# Current_Sense_Schematic.net
KiCad netlist of a schematic drawn in Altium Designer
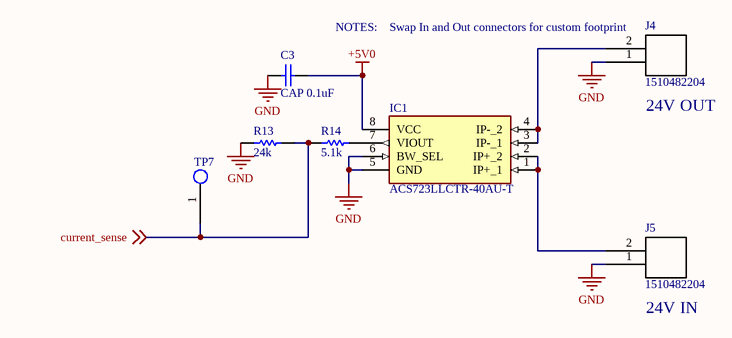
[diagram p0: Current Sense Schematic.SchDoc]

(export (version "E")
  (design (tool "Eeschema 10.0.6"))
  (components
    (comp (ref "C3")
      (value "CAP 0.1uF")
      (footprint "CAPC0805(2012)75_L")
      (description "CAP 2.7pF 50V ±0.1pF 0805 (2012 Metric) Thickness 0.75mm SMD")
      (fields (field (name "TOLERANCE") "Â±0.1pF"))
      (libsource (lib "Integrated_Library - 12.01.19 - 13.05") (part "CMP-1036-00339-1"))
    )
    (comp (ref "IC1")
      (value "ACS723LLCTR-40AU-T")
      (footprint "SOT127P600X175-8N")
      (description "Integrated Circuit")
      (libsource (lib "SamacSys") (part "ACS723LLCTR-40AU-T"))
    )
    (comp (ref "J4")
      (value "1510482204")
      (footprint "1510482204")
      (description "Molex 6.5MM 2 pin connector, used for power connections. P/N 1510482204 and similar models.")
      (libsource (lib "Molex 6.5MM  power connectors, 1510482204 etc.") (part "1510482204"))
    )
    (comp (ref "J5")
      (value "1510482204")
      (footprint "1510482204")
      (description "Molex 6.5MM 2 pin connector, used for power connections. P/N 1510482204 and similar models.")
      (libsource (lib "Molex 6.5MM  power connectors, 1510482204 etc.") (part "1510482204"))
    )
    (comp (ref "R13")
      (value "24k")
      (footprint "RESC2013X70X40LL20T20")
      (description "RES SMD 150K OHM 1% 1/8W 0805")
      (fields (field (name "MANUFACTURER") "Panasonic") (field (name "PART NUMBER") "ERJ-6ENF1503V"))
      (libsource (lib "Altium Content Vault") (part "RES"))
    )
    (comp (ref "R14")
      (value "5.1k")
      (footprint "RESC2013X70X40LL20T20")
      (description "RES SMD 150K OHM 1% 1/8W 0805")
      (fields (field (name "MANUFACTURER") "Panasonic") (field (name "PART NUMBER") "ERJ-6ENF1503V"))
      (libsource (lib "Altium Content Vault") (part "RES"))
    )
    (comp (ref "TP7")
      (value "Test Point")
      (footprint "Test Point Through-hole")
      (libsource (lib "Husky Robotics Standard Library 2019-2020") (part "Test Point"))
    )
  )
  (nets
    (net (code "1") (name "+5V0") (class "Default")
      (node (ref "C3") (pin "2") (pinfunction "2_2") (pintype "passive"))
      (node (ref "IC1") (pin "8") (pinfunction "VCC_8") (pintype "power_in"))
    )
    (net (code "2") (name "GND") (class "Default")
      (node (ref "C3") (pin "1") (pinfunction "1_1") (pintype "passive"))
      (node (ref "IC1") (pin "5") (pinfunction "GND_5") (pintype "power_in"))
      (node (ref "IC1") (pin "6") (pinfunction "BW_SEL_6") (pintype "input"))
      (node (ref "J4") (pin "1") (pintype "passive"))
      (node (ref "J5") (pin "1") (pintype "passive"))
      (node (ref "R13") (pin "2") (pinfunction "2_2") (pintype "passive"))
    )
    (net (code "3") (name "Net-(IC1-IP+_1)") (class "Default")
      (node (ref "IC1") (pin "1") (pinfunction "IP+_1_1") (pintype "input"))
      (node (ref "IC1") (pin "2") (pinfunction "IP+_2_2") (pintype "input"))
      (node (ref "J5") (pin "2") (pintype "passive"))
    )
    (net (code "4") (name "Net-(IC1-IP-_1)") (class "Default")
      (node (ref "IC1") (pin "3") (pinfunction "IP-_1_3") (pintype "input"))
      (node (ref "IC1") (pin "4") (pinfunction "IP-_2_4") (pintype "input"))
      (node (ref "J4") (pin "2") (pintype "passive"))
    )
    (net (code "5") (name "Net-(IC1-VIOUT)") (class "Default")
      (node (ref "IC1") (pin "7") (pinfunction "VIOUT_7") (pintype "output"))
      (node (ref "R14") (pin "1") (pinfunction "1_1") (pintype "passive"))
    )
    (net (code "6") (name "current_sense") (class "Default")
      (node (ref "R13") (pin "1") (pinfunction "1_1") (pintype "passive"))
      (node (ref "R14") (pin "2") (pinfunction "2_2") (pintype "passive"))
      (node (ref "TP7") (pin "1") (pinfunction "1_1") (pintype "passive"))
    )
  )
)
